# Adafruit_MAX4466_Mic_Amp.net
KiCad netlist of a schematic drawn in EAGLE
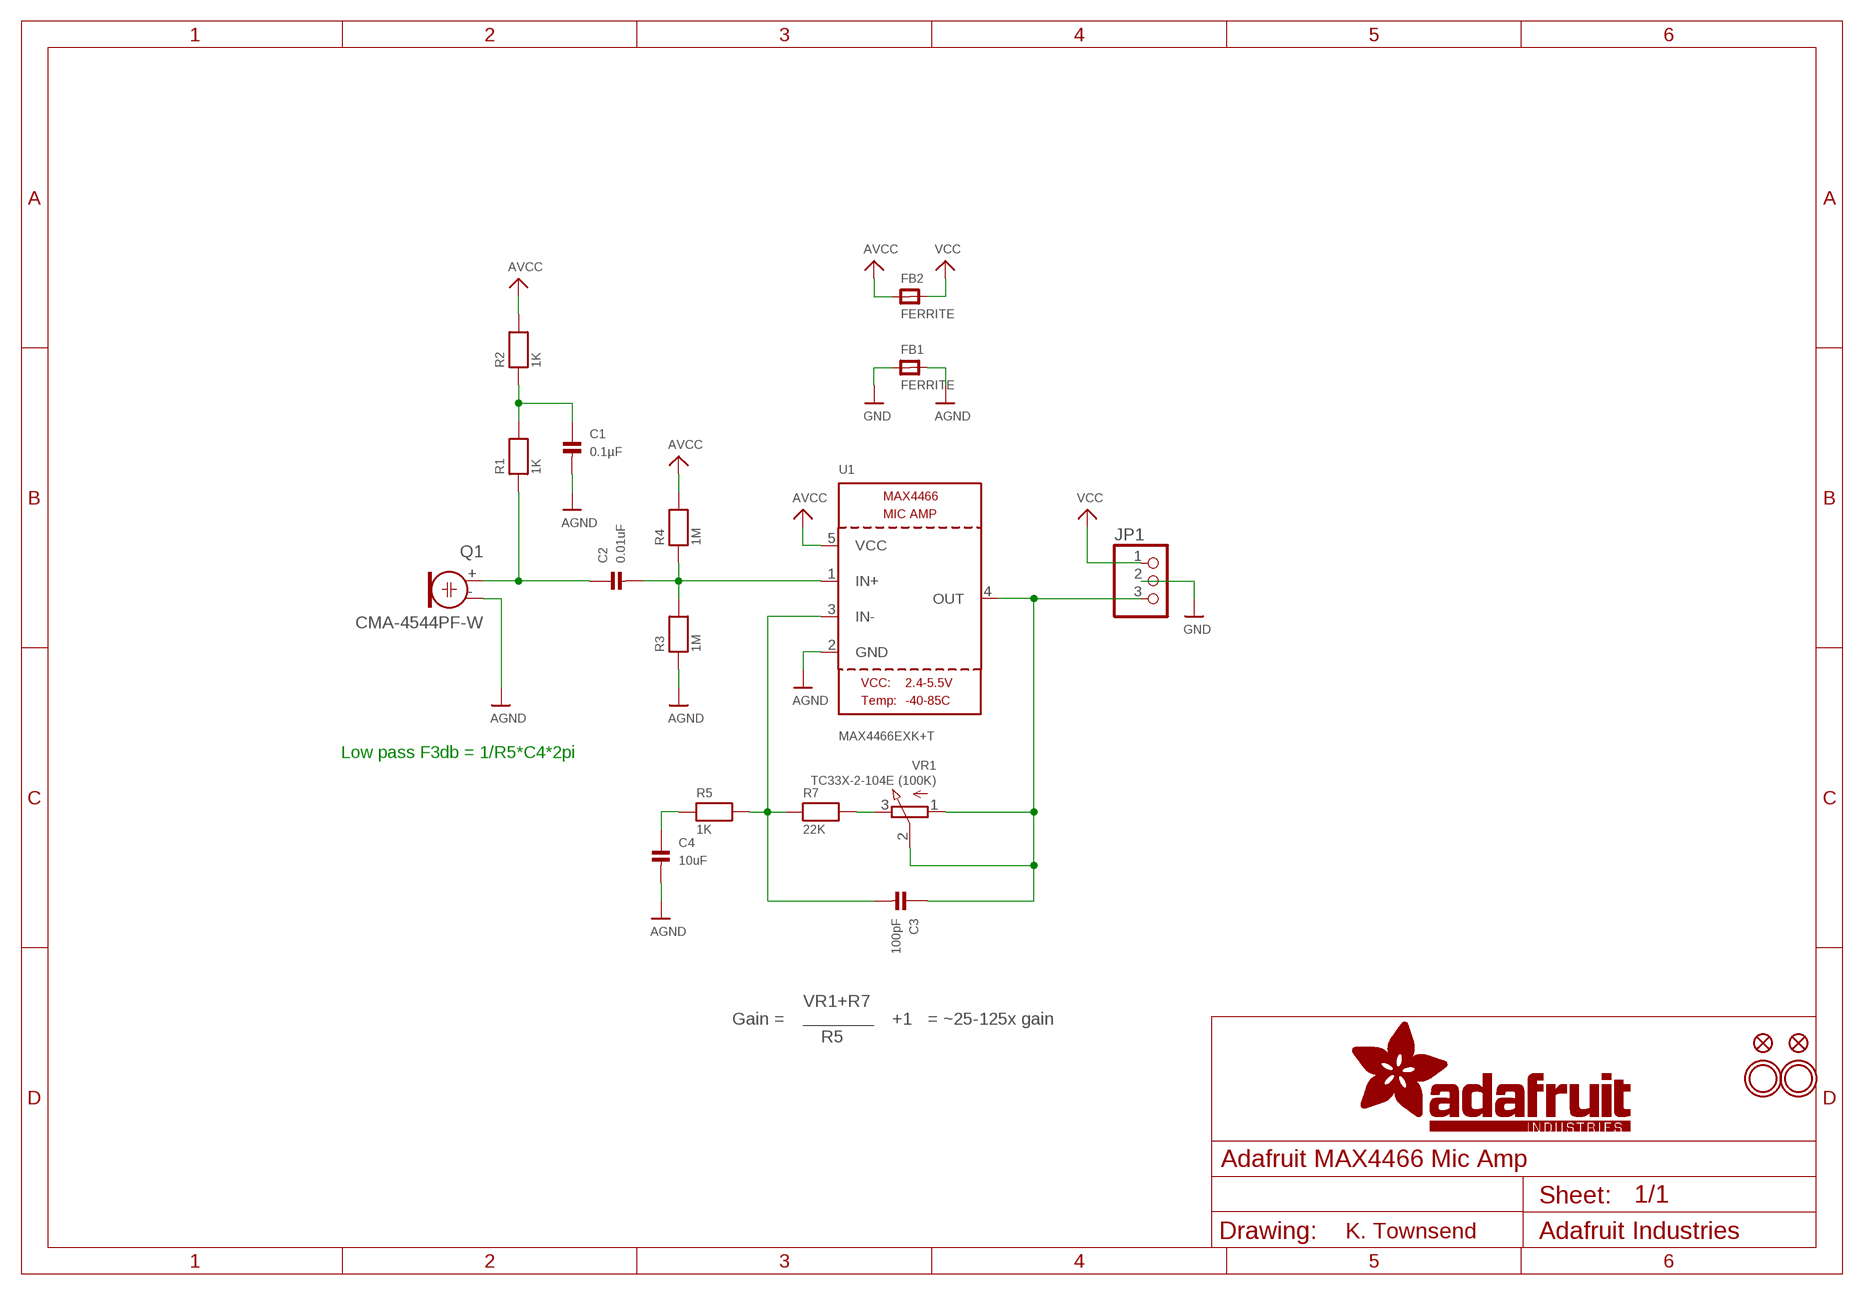
[diagram p0: schematic, sheet 1]

(export (version "E")
  (design (tool "Eeschema 10.0.6"))
  (components
    (comp (ref "C1")
      (value "0.1µF")
      (footprint "eagle-import:0805")
      (libsource (lib "eagle-import") (part "CAP_CERAMIC0805"))
    )
    (comp (ref "C2")
      (value "0.01uF")
      (footprint "eagle-import:0805")
      (libsource (lib "eagle-import") (part "CAP_CERAMIC0805"))
    )
    (comp (ref "C3")
      (value "100pF")
      (footprint "eagle-import:0805")
      (libsource (lib "eagle-import") (part "CAP_CERAMIC0805"))
    )
    (comp (ref "C4")
      (value "10uF")
      (footprint "eagle-import:0805")
      (libsource (lib "eagle-import") (part "CAP_CERAMIC0805"))
    )
    (comp (ref "FB1")
      (value "FERRITE")
      (footprint "eagle-import:0805")
      (libsource (lib "eagle-import") (part "FERRITE0805"))
    )
    (comp (ref "FB2")
      (value "FERRITE")
      (footprint "eagle-import:0805")
      (libsource (lib "eagle-import") (part "FERRITE0805"))
    )
    (comp (ref "FID1")
      (value "FIDUCIAL\"\"")
      (footprint "eagle-import:FIDUCIAL_1MM")
      (libsource (lib "eagle-import") (part "FIDUCIAL{dblquote}{dblquote}"))
    )
    (comp (ref "FID2")
      (value "FIDUCIAL\"\"")
      (footprint "eagle-import:FIDUCIAL_1MM")
      (libsource (lib "eagle-import") (part "FIDUCIAL{dblquote}{dblquote}"))
    )
    (comp (ref "JP1")
      (value "HEADER-1X376MIL")
      (footprint "eagle-import:1X03_ROUND_76")
      (libsource (lib "eagle-import") (part "HEADER-1X376MIL"))
    )
    (comp (ref "Q1")
      (value "CMA-4544PF-W")
      (footprint "eagle-import:ELECTRET_9.7")
      (libsource (lib "eagle-import") (part "ELECTRET"))
    )
    (comp (ref "R1")
      (value "1K")
      (footprint "eagle-import:0805")
      (libsource (lib "eagle-import") (part "RESISTOR0805"))
    )
    (comp (ref "R2")
      (value "1K")
      (footprint "eagle-import:0805")
      (libsource (lib "eagle-import") (part "RESISTOR0805"))
    )
    (comp (ref "R3")
      (value "1M")
      (footprint "eagle-import:0805")
      (libsource (lib "eagle-import") (part "RESISTOR0805"))
    )
    (comp (ref "R4")
      (value "1M")
      (footprint "eagle-import:0805")
      (libsource (lib "eagle-import") (part "RESISTOR0805"))
    )
    (comp (ref "R5")
      (value "1K")
      (footprint "eagle-import:0805")
      (libsource (lib "eagle-import") (part "RESISTOR0805"))
    )
    (comp (ref "R7")
      (value "22K")
      (footprint "eagle-import:0805")
      (libsource (lib "eagle-import") (part "RESISTOR0805"))
    )
    (comp (ref "U$11")
      (value "MOUNTINGHOLE2.5")
      (footprint "eagle-import:MOUNTINGHOLE_2.5_PLATED")
      (libsource (lib "eagle-import") (part "MOUNTINGHOLE2.5"))
    )
    (comp (ref "U$14")
      (value "MOUNTINGHOLE2.5")
      (footprint "eagle-import:MOUNTINGHOLE_2.5_PLATED")
      (libsource (lib "eagle-import") (part "MOUNTINGHOLE2.5"))
    )
    (comp (ref "U1")
      (value "MAX4466EXK+T")
      (footprint "eagle-import:SC70-5")
      (libsource (lib "eagle-import") (part "MAX4466{dblquote}{dblquote}"))
    )
    (comp (ref "VR1")
      (value "TC33X-2-104E (100K)")
      (footprint "eagle-import:TRIMPOT_BOURNS_TC33X-2")
      (libsource (lib "eagle-import") (part "TRIMPOTTC33X-2"))
    )
  )
  (nets
    (net (code "1") (name "AGND") (class "Default")
      (node (ref "C1") (pin "2") (pinfunction "P$2_2") (pintype "passive"))
      (node (ref "C4") (pin "2") (pinfunction "P$2_2") (pintype "passive"))
      (node (ref "FB1") (pin "2") (pinfunction "P$2_2") (pintype "passive"))
      (node (ref "Q1") (pin "-") (pinfunction "1_-") (pintype "passive"))
      (node (ref "R3") (pin "1") (pinfunction "1_1") (pintype "passive"))
      (node (ref "U1") (pin "2") (pinfunction "GND_2") (pintype "bidirectional"))
    )
    (net (code "2") (name "AVCC") (class "Default")
      (node (ref "FB2") (pin "1") (pinfunction "P$1_1") (pintype "passive"))
      (node (ref "R2") (pin "2") (pinfunction "2_2") (pintype "passive"))
      (node (ref "R4") (pin "2") (pinfunction "2_2") (pintype "passive"))
      (node (ref "U1") (pin "5") (pinfunction "VCC_5") (pintype "bidirectional"))
    )
    (net (code "3") (name "GND") (class "Default")
      (node (ref "FB1") (pin "1") (pinfunction "P$1_1") (pintype "passive"))
      (node (ref "JP1") (pin "2") (pinfunction "2_2") (pintype "passive"))
    )
    (net (code "4") (name "Net-(C1-P$1)") (class "Default")
      (node (ref "C1") (pin "1") (pinfunction "P$1_1") (pintype "passive"))
      (node (ref "R1") (pin "2") (pinfunction "2_2") (pintype "passive"))
      (node (ref "R2") (pin "1") (pinfunction "1_1") (pintype "passive"))
    )
    (net (code "5") (name "Net-(C2-P$1)") (class "Default")
      (node (ref "C2") (pin "1") (pinfunction "P$1_1") (pintype "passive"))
      (node (ref "Q1") (pin "+") (pinfunction "2_+") (pintype "passive"))
      (node (ref "R1") (pin "1") (pinfunction "1_1") (pintype "passive"))
    )
    (net (code "6") (name "Net-(C2-P$2)") (class "Default")
      (node (ref "C2") (pin "2") (pinfunction "P$2_2") (pintype "passive"))
      (node (ref "R3") (pin "2") (pinfunction "2_2") (pintype "passive"))
      (node (ref "R4") (pin "1") (pinfunction "1_1") (pintype "passive"))
      (node (ref "U1") (pin "1") (pinfunction "IN+_1") (pintype "bidirectional"))
    )
    (net (code "7") (name "Net-(C3-P$1)") (class "Default")
      (node (ref "C3") (pin "1") (pinfunction "P$1_1") (pintype "passive"))
      (node (ref "JP1") (pin "3") (pinfunction "3_3") (pintype "passive"))
      (node (ref "U1") (pin "4") (pinfunction "OUT_4") (pintype "bidirectional"))
      (node (ref "VR1") (pin "1") (pinfunction "A_1") (pintype "passive"))
      (node (ref "VR1") (pin "2") (pinfunction "S_2") (pintype "passive"))
    )
    (net (code "8") (name "Net-(C3-P$2)") (class "Default")
      (node (ref "C3") (pin "2") (pinfunction "P$2_2") (pintype "passive"))
      (node (ref "R5") (pin "2") (pinfunction "2_2") (pintype "passive"))
      (node (ref "R7") (pin "1") (pinfunction "1_1") (pintype "passive"))
      (node (ref "U1") (pin "3") (pinfunction "IN-_3") (pintype "bidirectional"))
    )
    (net (code "9") (name "Net-(C4-P$1)") (class "Default")
      (node (ref "C4") (pin "1") (pinfunction "P$1_1") (pintype "passive"))
      (node (ref "R5") (pin "1") (pinfunction "1_1") (pintype "passive"))
    )
    (net (code "10") (name "Net-(VR1-E)") (class "Default")
      (node (ref "R7") (pin "2") (pinfunction "2_2") (pintype "passive"))
      (node (ref "VR1") (pin "3") (pinfunction "E_3") (pintype "passive"))
    )
    (net (code "11") (name "VCC") (class "Default")
      (node (ref "FB2") (pin "2") (pinfunction "P$2_2") (pintype "passive"))
      (node (ref "JP1") (pin "1") (pinfunction "1_1") (pintype "passive"))
    )
  )
)
